# level_shifter.net
KiCad netlist of a schematic drawn in EAGLE
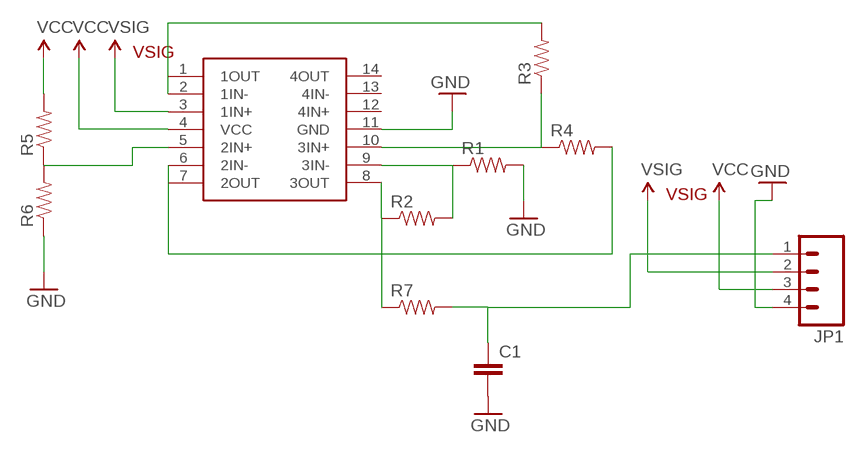
[diagram p0: schematic, sheet 1]

(export (version "E")
  (design (tool "Eeschema 10.0.6"))
  (components
    (comp (ref "C1")
      (value "CAPPTH1")
      (footprint "eagle-import:CAP-PTH-5MM")
      (libsource (lib "eagle-import") (part "CAPPTH1"))
    )
    (comp (ref "JP1")
      (value "M04SCREW-5MM")
      (footprint "eagle-import:SCREWTERMINAL-5MM-4")
      (libsource (lib "eagle-import") (part "M04SCREW-5MM"))
    )
    (comp (ref "R1")
      (value "RESISTORPTH-1/4W")
      (footprint "eagle-import:AXIAL-0.4")
      (libsource (lib "eagle-import") (part "RESISTORPTH-1/4W"))
    )
    (comp (ref "R2")
      (value "RESISTORPTH-1/4W")
      (footprint "eagle-import:AXIAL-0.4")
      (libsource (lib "eagle-import") (part "RESISTORPTH-1/4W"))
    )
    (comp (ref "R3")
      (value "RESISTORPTH-1/4W")
      (footprint "eagle-import:AXIAL-0.4")
      (libsource (lib "eagle-import") (part "RESISTORPTH-1/4W"))
    )
    (comp (ref "R4")
      (value "RESISTORPTH-1/4W")
      (footprint "eagle-import:AXIAL-0.4")
      (libsource (lib "eagle-import") (part "RESISTORPTH-1/4W"))
    )
    (comp (ref "R5")
      (value "RESISTORPTH-1/4W")
      (footprint "eagle-import:AXIAL-0.4")
      (libsource (lib "eagle-import") (part "RESISTORPTH-1/4W"))
    )
    (comp (ref "R6")
      (value "RESISTORPTH-1/4W")
      (footprint "eagle-import:AXIAL-0.4")
      (libsource (lib "eagle-import") (part "RESISTORPTH-1/4W"))
    )
    (comp (ref "R7")
      (value "RESISTORPTH-1/4W")
      (footprint "eagle-import:AXIAL-0.4")
      (libsource (lib "eagle-import") (part "RESISTORPTH-1/4W"))
    )
    (comp (ref "U$1")
      (value "LM324DIP")
      (footprint "eagle-import:DIL14")
      (libsource (lib "eagle-import") (part "LM324DIP"))
    )
  )
  (nets
    (net (code "1") (name "GND") (class "Default")
      (node (ref "C1") (pin "2") (pinfunction "2_2") (pintype "passive"))
      (node (ref "JP1") (pin "4") (pinfunction "4_4") (pintype "passive"))
      (node (ref "R1") (pin "P$2") (pinfunction "2_P$2") (pintype "passive"))
      (node (ref "R6") (pin "P$1") (pinfunction "1_P$1") (pintype "passive"))
      (node (ref "U$1") (pin "11") (pinfunction "GND_11") (pintype "bidirectional"))
    )
    (net (code "2") (name "Net-(R1-1)") (class "Default")
      (node (ref "R1") (pin "P$1") (pinfunction "1_P$1") (pintype "passive"))
      (node (ref "R2") (pin "P$2") (pinfunction "2_P$2") (pintype "passive"))
      (node (ref "U$1") (pin "9") (pinfunction "3IN-_9") (pintype "bidirectional"))
    )
    (net (code "3") (name "Net-(R2-1)") (class "Default")
      (node (ref "R2") (pin "P$1") (pinfunction "1_P$1") (pintype "passive"))
      (node (ref "R7") (pin "P$1") (pinfunction "1_P$1") (pintype "passive"))
      (node (ref "U$1") (pin "8") (pinfunction "3OUT_8") (pintype "bidirectional"))
    )
    (net (code "4") (name "Net-(R3-1)") (class "Default")
      (node (ref "R3") (pin "P$1") (pinfunction "1_P$1") (pintype "passive"))
      (node (ref "R4") (pin "P$1") (pinfunction "1_P$1") (pintype "passive"))
      (node (ref "U$1") (pin "10") (pinfunction "3IN+_10") (pintype "bidirectional"))
    )
    (net (code "5") (name "Net-(R3-2)") (class "Default")
      (node (ref "R3") (pin "P$2") (pinfunction "2_P$2") (pintype "passive"))
      (node (ref "U$1") (pin "1") (pinfunction "1OUT_1") (pintype "bidirectional"))
      (node (ref "U$1") (pin "2") (pinfunction "1IN-_2") (pintype "bidirectional"))
    )
    (net (code "6") (name "Net-(R4-2)") (class "Default")
      (node (ref "R4") (pin "P$2") (pinfunction "2_P$2") (pintype "passive"))
      (node (ref "U$1") (pin "6") (pinfunction "2IN-_6") (pintype "bidirectional"))
      (node (ref "U$1") (pin "7") (pinfunction "2OUT_7") (pintype "bidirectional"))
    )
    (net (code "7") (name "Net-(R5-1)") (class "Default")
      (node (ref "R5") (pin "P$1") (pinfunction "1_P$1") (pintype "passive"))
      (node (ref "R6") (pin "P$2") (pinfunction "2_P$2") (pintype "passive"))
      (node (ref "U$1") (pin "5") (pinfunction "2IN+_5") (pintype "bidirectional"))
    )
    (net (code "8") (name "Net-(R7-2)") (class "Default")
      (node (ref "C1") (pin "1") (pinfunction "1_1") (pintype "passive"))
      (node (ref "JP1") (pin "1") (pinfunction "1_1") (pintype "passive"))
      (node (ref "R7") (pin "P$2") (pinfunction "2_P$2") (pintype "passive"))
    )
    (net (code "9") (name "VCC") (class "Default")
      (node (ref "JP1") (pin "3") (pinfunction "3_3") (pintype "passive"))
      (node (ref "R5") (pin "P$2") (pinfunction "2_P$2") (pintype "passive"))
      (node (ref "U$1") (pin "4") (pinfunction "VCC_4") (pintype "bidirectional"))
    )
    (net (code "10") (name "VSIG") (class "Default")
      (node (ref "JP1") (pin "2") (pinfunction "2_2") (pintype "passive"))
      (node (ref "U$1") (pin "3") (pinfunction "1IN+_3") (pintype "bidirectional"))
    )
    (net (code "11") (name "unconnected-(U$1-4IN+-Pad12)") (class "Default")
      (node (ref "U$1") (pin "12") (pinfunction "4IN+_12") (pintype "bidirectional"))
    )
    (net (code "12") (name "unconnected-(U$1-4IN--Pad13)") (class "Default")
      (node (ref "U$1") (pin "13") (pinfunction "4IN-_13") (pintype "bidirectional"))
    )
    (net (code "13") (name "unconnected-(U$1-4OUT-Pad14)") (class "Default")
      (node (ref "U$1") (pin "14") (pinfunction "4OUT_14") (pintype "bidirectional"))
    )
  )
)
